# GU154X39LOL.net
KiCad netlist of a schematic drawn in EAGLE
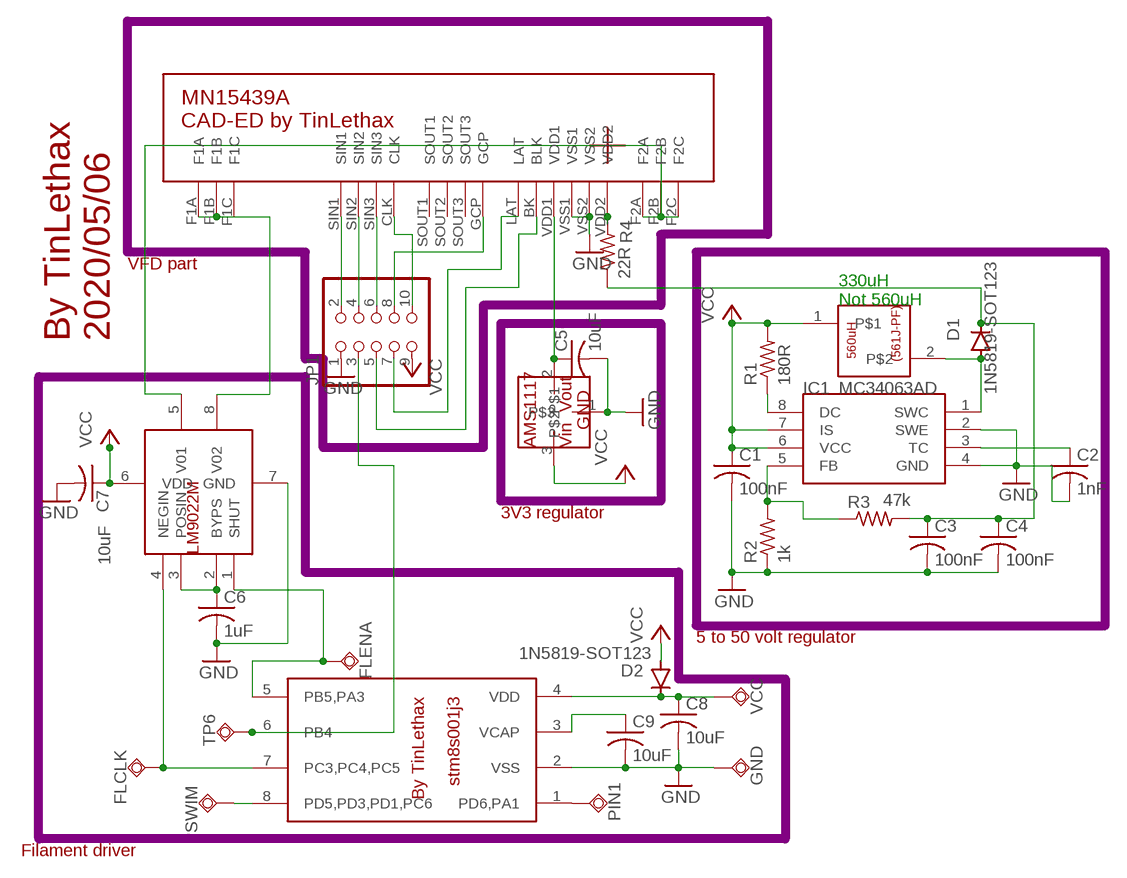
[diagram p0: schematic, sheet 1]

(export (version "E")
  (design (tool "Eeschema 10.0.6"))
  (components
    (comp (ref "330UH1210")
      (value "330uH")
      (footprint "eagle-import:INDC4526X50N")
      (libsource (lib "eagle-import") (part "NL453232T-561J-PF"))
    )
    (comp (ref "C1")
      (value "100nF")
      (footprint "eagle-import:C1206K")
      (libsource (lib "eagle-import") (part "C-USC1206K"))
    )
    (comp (ref "C2")
      (value "1nF")
      (footprint "eagle-import:C0805")
      (libsource (lib "eagle-import") (part "capsmd_C-USC0805"))
    )
    (comp (ref "C3")
      (value "100nF")
      (footprint "eagle-import:C1206K")
      (libsource (lib "eagle-import") (part "C-USC1206K"))
    )
    (comp (ref "C4")
      (value "100nF")
      (footprint "eagle-import:C1206K")
      (libsource (lib "eagle-import") (part "C-USC1206K"))
    )
    (comp (ref "C5")
      (value "10uF")
      (footprint "eagle-import:C0805")
      (libsource (lib "eagle-import") (part "capsmd_C-USC0805"))
    )
    (comp (ref "C6")
      (value "1uF")
      (footprint "eagle-import:C0805")
      (libsource (lib "eagle-import") (part "capsmd_C-USC0805"))
    )
    (comp (ref "C7")
      (value "10uF")
      (footprint "eagle-import:C0805")
      (libsource (lib "eagle-import") (part "capsmd_C-USC0805"))
    )
    (comp (ref "C8")
      (value "10uF")
      (footprint "eagle-import:C0805")
      (libsource (lib "eagle-import") (part "capsmd_C-USC0805"))
    )
    (comp (ref "C9")
      (value "10uF")
      (footprint "eagle-import:C0805")
      (libsource (lib "eagle-import") (part "capsmd_C-USC0805"))
    )
    (comp (ref "D1")
      (value "1N5819-SOT123")
      (footprint "eagle-import:SOD-123_MINI-SMA")
      (libsource (lib "eagle-import") (part "CGRM400-G"))
    )
    (comp (ref "D2")
      (value "1N5819-SOT123")
      (footprint "eagle-import:SOD-123_MINI-SMA")
      (libsource (lib "eagle-import") (part "CGRM400-G"))
    )
    (comp (ref "FLCLK")
      (value "TPSQTP20SQ")
      (footprint "eagle-import:TP20SQ")
      (libsource (lib "eagle-import") (part "TPSQTP20SQ"))
    )
    (comp (ref "FLENA")
      (value "TPSQTP20SQ")
      (footprint "eagle-import:TP20SQ")
      (libsource (lib "eagle-import") (part "TPSQTP20SQ"))
    )
    (comp (ref "GND")
      (value "TPSQTP20SQ")
      (footprint "eagle-import:TP20SQ")
      (libsource (lib "eagle-import") (part "TPSQTP20SQ"))
    )
    (comp (ref "IC1")
      (value "MC34063AD")
      (footprint "eagle-import:SOIC8")
      (libsource (lib "eagle-import") (part "MC34063AD"))
    )
    (comp (ref "IC2")
      (value "STM8S001J3")
      (footprint "eagle-import:SOP8")
      (libsource (lib "eagle-import") (part "STM8S001J3"))
    )
    (comp (ref "IC3")
      (value "LM9022M")
      (footprint "eagle-import:SOIC127P590X265-8N")
      (fields (field (name "PARTNO") "LM9022"))
      (libsource (lib "eagle-import") (part "LM9022M"))
    )
    (comp (ref "IC4")
      (value "AMS1117")
      (footprint "eagle-import:SOT223")
      (libsource (lib "eagle-import") (part "AMS1117"))
    )
    (comp (ref "JP1")
      (value "PINHD-2X5")
      (footprint "eagle-import:2X05")
      (libsource (lib "eagle-import") (part "PINHD-2X5"))
    )
    (comp (ref "PIN1")
      (value "TPSQTP20SQ")
      (footprint "eagle-import:TP20SQ")
      (libsource (lib "eagle-import") (part "TPSQTP20SQ"))
    )
    (comp (ref "R1")
      (value "180R")
      (footprint "eagle-import:R0805")
      (libsource (lib "eagle-import") (part "R-US_R0805"))
    )
    (comp (ref "R2")
      (value "1k")
      (footprint "eagle-import:R0805")
      (libsource (lib "eagle-import") (part "R-US_R0805"))
    )
    (comp (ref "R3")
      (value "47k")
      (footprint "eagle-import:R0805")
      (libsource (lib "eagle-import") (part "R-US_R0805"))
    )
    (comp (ref "R4")
      (value "22R")
      (footprint "eagle-import:R0805")
      (libsource (lib "eagle-import") (part "R-US_R0805"))
    )
    (comp (ref "SWIM")
      (value "TPSQTP20SQ")
      (footprint "eagle-import:TP20SQ")
      (libsource (lib "eagle-import") (part "TPSQTP20SQ"))
    )
    (comp (ref "TP6")
      (value "TPSQTP20SQ")
      (footprint "eagle-import:TP20SQ")
      (libsource (lib "eagle-import") (part "TPSQTP20SQ"))
    )
    (comp (ref "U$1")
      (value "MN15439A")
      (footprint "eagle-import:THT-20")
      (libsource (lib "eagle-import") (part "MN15439A"))
    )
    (comp (ref "VCC")
      (value "TPSQTP20SQ")
      (footprint "eagle-import:TP20SQ")
      (libsource (lib "eagle-import") (part "TPSQTP20SQ"))
    )
  )
  (nets
    (net (code "1") (name "GND") (class "Default")
      (node (ref "C1") (pin "2") (pinfunction "2_2") (pintype "passive"))
      (node (ref "C2") (pin "2") (pinfunction "2_2") (pintype "passive"))
      (node (ref "C3") (pin "2") (pinfunction "2_2") (pintype "passive"))
      (node (ref "C4") (pin "2") (pinfunction "2_2") (pintype "passive"))
      (node (ref "C5") (pin "2") (pinfunction "2_2") (pintype "passive"))
      (node (ref "C6") (pin "2") (pinfunction "2_2") (pintype "passive"))
      (node (ref "C7") (pin "2") (pinfunction "2_2") (pintype "passive"))
      (node (ref "C8") (pin "2") (pinfunction "2_2") (pintype "passive"))
      (node (ref "C9") (pin "2") (pinfunction "2_2") (pintype "passive"))
      (node (ref "GND") (pin "TP") (pinfunction "TP_TP") (pintype "input"))
      (node (ref "IC1") (pin "2") (pinfunction "SWE_2") (pintype "passive"))
      (node (ref "IC1") (pin "4") (pinfunction "GND_4") (pintype "passive"))
      (node (ref "IC2") (pin "2") (pinfunction "VSS_2") (pintype "bidirectional"))
      (node (ref "IC3") (pin "7") (pinfunction "GND_7") (pintype "bidirectional"))
      (node (ref "IC4") (pin "1") (pinfunction "P$3_1") (pintype "bidirectional"))
      (node (ref "JP1") (pin "1") (pinfunction "1_1") (pintype "passive"))
      (node (ref "R2") (pin "1") (pinfunction "1_1") (pintype "passive"))
      (node (ref "U$1") (pin "VSS1") (pinfunction "VSS1_VSS1") (pintype "bidirectional"))
      (node (ref "U$1") (pin "VSS2") (pinfunction "VSS2_VSS2") (pintype "bidirectional"))
    )
    (net (code "2") (name "Net-(330UH1210-P$2)") (class "Default")
      (node (ref "330UH1210") (pin "2") (pinfunction "P$2_2") (pintype "bidirectional"))
      (node (ref "D1") (pin "A") (pinfunction "A_A") (pintype "passive"))
      (node (ref "IC1") (pin "1") (pinfunction "SWC_1") (pintype "passive"))
    )
    (net (code "3") (name "Net-(C3-Pad1)") (class "Default")
      (node (ref "C3") (pin "1") (pinfunction "1_1") (pintype "passive"))
      (node (ref "C4") (pin "1") (pinfunction "1_1") (pintype "passive"))
      (node (ref "D1") (pin "C") (pinfunction "C_C") (pintype "passive"))
      (node (ref "R3") (pin "2") (pinfunction "2_2") (pintype "passive"))
      (node (ref "R4") (pin "1") (pinfunction "1_1") (pintype "passive"))
    )
    (net (code "4") (name "Net-(IC1-DC)") (class "Default")
      (node (ref "IC1") (pin "8") (pinfunction "DC_8") (pintype "passive"))
      (node (ref "R1") (pin "1") (pinfunction "1_1") (pintype "passive"))
    )
    (net (code "5") (name "Net-(IC1-FB)") (class "Default")
      (node (ref "IC1") (pin "5") (pinfunction "FB_5") (pintype "passive"))
      (node (ref "R2") (pin "2") (pinfunction "2_2") (pintype "passive"))
      (node (ref "R3") (pin "1") (pinfunction "1_1") (pintype "passive"))
    )
    (net (code "6") (name "Net-(IC1-TC)") (class "Default")
      (node (ref "C2") (pin "1") (pinfunction "1_1") (pintype "passive"))
      (node (ref "IC1") (pin "3") (pinfunction "TC_3") (pintype "passive"))
    )
    (net (code "7") (name "Net-(IC2-PB4)") (class "Default")
      (node (ref "IC2") (pin "6") (pinfunction "PB4_6") (pintype "bidirectional"))
      (node (ref "JP1") (pin "3") (pinfunction "3_3") (pintype "passive"))
      (node (ref "TP6") (pin "TP") (pinfunction "TP_TP") (pintype "input"))
    )
    (net (code "8") (name "Net-(IC2-PB5,PA3)") (class "Default")
      (node (ref "FLENA") (pin "TP") (pinfunction "TP_TP") (pintype "input"))
      (node (ref "IC2") (pin "5") (pinfunction "PB5,PA3_5") (pintype "bidirectional"))
      (node (ref "IC3") (pin "1") (pinfunction "SHUT_1") (pintype "bidirectional"))
    )
    (net (code "9") (name "Net-(IC2-PC3,PC4,PC5)") (class "Default")
      (node (ref "FLCLK") (pin "TP") (pinfunction "TP_TP") (pintype "input"))
      (node (ref "IC2") (pin "7") (pinfunction "PC3,PC4,PC5_7") (pintype "bidirectional"))
      (node (ref "IC3") (pin "4") (pinfunction "NEGIN_4") (pintype "bidirectional"))
    )
    (net (code "10") (name "Net-(IC2-PD5,PD3,PD1,PC6)") (class "Default")
      (node (ref "IC2") (pin "8") (pinfunction "PD5,PD3,PD1,PC6_8") (pintype "bidirectional"))
      (node (ref "SWIM") (pin "TP") (pinfunction "TP_TP") (pintype "input"))
    )
    (net (code "11") (name "Net-(IC2-PD6,PA1)") (class "Default")
      (node (ref "IC2") (pin "1") (pinfunction "PD6,PA1_1") (pintype "bidirectional"))
      (node (ref "PIN1") (pin "TP") (pinfunction "TP_TP") (pintype "input"))
    )
    (net (code "12") (name "Net-(IC2-VCAP)") (class "Default")
      (node (ref "C9") (pin "1") (pinfunction "1_1") (pintype "passive"))
      (node (ref "IC2") (pin "3") (pinfunction "VCAP_3") (pintype "bidirectional"))
    )
    (net (code "13") (name "Net-(IC2-VDD)") (class "Default")
      (node (ref "C8") (pin "1") (pinfunction "1_1") (pintype "passive"))
      (node (ref "D2") (pin "C") (pinfunction "C_C") (pintype "passive"))
      (node (ref "IC2") (pin "4") (pinfunction "VDD_4") (pintype "bidirectional"))
      (node (ref "VCC") (pin "TP") (pinfunction "TP_TP") (pintype "input"))
    )
    (net (code "14") (name "Net-(IC3-BYPS)") (class "Default")
      (node (ref "C6") (pin "1") (pinfunction "1_1") (pintype "passive"))
      (node (ref "IC3") (pin "2") (pinfunction "BYPS_2") (pintype "bidirectional"))
      (node (ref "IC3") (pin "3") (pinfunction "POSIN_3") (pintype "bidirectional"))
    )
    (net (code "15") (name "Net-(IC3-V01)") (class "Default")
      (node (ref "IC3") (pin "5") (pinfunction "V01_5") (pintype "bidirectional"))
      (node (ref "U$1") (pin "F2A") (pinfunction "F2A_F2A") (pintype "bidirectional"))
      (node (ref "U$1") (pin "F2B") (pinfunction "F2B_F2B") (pintype "bidirectional"))
      (node (ref "U$1") (pin "F2C") (pinfunction "F2C_F2C") (pintype "bidirectional"))
    )
    (net (code "16") (name "Net-(IC3-V02)") (class "Default")
      (node (ref "IC3") (pin "8") (pinfunction "V02_8") (pintype "bidirectional"))
      (node (ref "U$1") (pin "F1A") (pinfunction "F1A_F1A") (pintype "bidirectional"))
      (node (ref "U$1") (pin "F1B") (pinfunction "F1B_F1B") (pintype "bidirectional"))
      (node (ref "U$1") (pin "F1C") (pinfunction "F1C_F1C") (pintype "bidirectional"))
    )
    (net (code "17") (name "Net-(IC4-P$2)") (class "Default")
      (node (ref "C5") (pin "1") (pinfunction "1_1") (pintype "passive"))
      (node (ref "IC4") (pin "2") (pinfunction "P$2_2") (pintype "bidirectional"))
      (node (ref "U$1") (pin "VDD1") (pinfunction "VDD1_VDD1") (pintype "bidirectional"))
    )
    (net (code "18") (name "Net-(JP1-Pad2)") (class "Default")
      (node (ref "JP1") (pin "2") (pinfunction "2_2") (pintype "passive"))
      (node (ref "U$1") (pin "SIN1") (pinfunction "SIN1_SIN1") (pintype "bidirectional"))
    )
    (net (code "19") (name "Net-(JP1-Pad4)") (class "Default")
      (node (ref "JP1") (pin "4") (pinfunction "4_4") (pintype "passive"))
      (node (ref "U$1") (pin "SIN2") (pinfunction "SIN2_SIN2") (pintype "bidirectional"))
    )
    (net (code "20") (name "Net-(JP1-Pad6)") (class "Default")
      (node (ref "JP1") (pin "6") (pinfunction "6_6") (pintype "passive"))
      (node (ref "U$1") (pin "SIN3") (pinfunction "SIN3_SIN3") (pintype "bidirectional"))
    )
    (net (code "21") (name "Net-(JP1-Pad7)") (class "Default")
      (node (ref "JP1") (pin "7") (pinfunction "7_7") (pintype "passive"))
      (node (ref "U$1") (pin "LAT") (pinfunction "LAT_LAT") (pintype "bidirectional"))
    )
    (net (code "22") (name "Net-(JP1-Pad8)") (class "Default")
      (node (ref "JP1") (pin "8") (pinfunction "8_8") (pintype "passive"))
      (node (ref "U$1") (pin "GCP") (pinfunction "GCP_GCP") (pintype "bidirectional"))
    )
    (net (code "23") (name "Net-(JP1-Pad10)") (class "Default")
      (node (ref "JP1") (pin "10") (pinfunction "10_10") (pintype "passive"))
      (node (ref "U$1") (pin "CLK") (pinfunction "CLK_CLK") (pintype "bidirectional"))
    )
    (net (code "24") (name "Net-(R4-Pad2)") (class "Default")
      (node (ref "R4") (pin "2") (pinfunction "2_2") (pintype "passive"))
      (node (ref "U$1") (pin "VDD2") (pinfunction "VDD2_VDD2") (pintype "bidirectional"))
    )
    (net (code "25") (name "Net-(U$1-BLK)") (class "Default")
      (node (ref "JP1") (pin "5") (pinfunction "5_5") (pintype "passive"))
      (node (ref "U$1") (pin "BK") (pinfunction "BLK_BK") (pintype "bidirectional"))
    )
    (net (code "26") (name "VCC") (class "Default")
      (node (ref "330UH1210") (pin "1") (pinfunction "P$1_1") (pintype "bidirectional"))
      (node (ref "C1") (pin "1") (pinfunction "1_1") (pintype "passive"))
      (node (ref "C7") (pin "1") (pinfunction "1_1") (pintype "passive"))
      (node (ref "D2") (pin "A") (pinfunction "A_A") (pintype "passive"))
      (node (ref "IC1") (pin "6") (pinfunction "VCC_6") (pintype "passive"))
      (node (ref "IC1") (pin "7") (pinfunction "IS_7") (pintype "passive"))
      (node (ref "IC3") (pin "6") (pinfunction "VDD_6") (pintype "bidirectional"))
      (node (ref "IC4") (pin "3") (pinfunction "P$1_3") (pintype "bidirectional"))
      (node (ref "JP1") (pin "9") (pinfunction "9_9") (pintype "passive"))
      (node (ref "R1") (pin "2") (pinfunction "2_2") (pintype "passive"))
    )
    (net (code "27") (name "unconnected-(U$1-PadSOUT1)") (class "Default")
      (node (ref "U$1") (pin "SOUT1") (pinfunction "SOUT1_SOUT1") (pintype "bidirectional"))
    )
    (net (code "28") (name "unconnected-(U$1-PadSOUT2)") (class "Default")
      (node (ref "U$1") (pin "SOUT2") (pinfunction "SOUT2_SOUT2") (pintype "bidirectional"))
    )
    (net (code "29") (name "unconnected-(U$1-PadSOUT3)") (class "Default")
      (node (ref "U$1") (pin "SOUT3") (pinfunction "SOUT3_SOUT3") (pintype "bidirectional"))
    )
  )
)
